# CAN1.net
KiCad netlist of a schematic drawn in Altium Designer
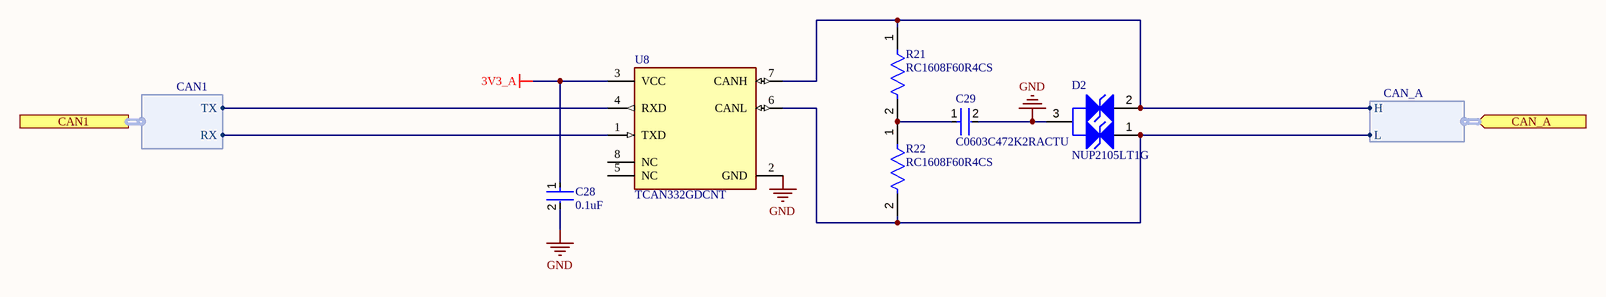
[diagram p0: CAN1.SchDoc]

(export (version "E")
  (design (tool "Eeschema 10.0.6"))
  (components
    (comp (ref "C28")
      (value "0.1uF")
      (footprint "FP-C0603C-CF-MFG")
      (description "CAP CER 0.1UF 50V X7R 0603")
      (fields (field (name "TOLERANCE") "0.1") (field (name "MANUFACTURER") "KEMET"))
      (libsource (lib "Altium Content Vault") (part "b4654b650e69147ec39a6b967a45e02"))
    )
    (comp (ref "C29")
      (value "C0603C472K2RACTU")
      (footprint "FP-C0603C-CF-MFG")
      (description "CAP CER 4700PF 200V 10% X7R 0603")
      (fields
        (field (name "OCTOPART") "https://octopart.com/c0603c472k2ractu-kemet-17058096")
        (field (name "MANUFACTURER") "KEMET")
      )
      (libsource (lib "Altium Content Vault") (part "b4654b650e69147ec39a6b967a45e02"))
    )
    (comp (ref "D2")
      (value "NUP2105LT1G")
      (footprint "ONSC-SOT-23-3-318-08_V")
      (description "Dual Line CAN Bus Protector, 3-Pin SOT-23, Pb-Free, Tape and Reel")
      (fields (field (name "MANUFACTURER") "On Semiconductor"))
      (libsource (lib "Altium Content Vault") (part "ONSC-NUP21X5X-SOT-23-3-318-08"))
    )
    (comp (ref "R21")
      (value "RC1608F60R4CS")
      (footprint "FP-RC1608-IPC_C")
      (description "Res Thick Film 0603 60.4Ω 1% 0.1W ±100ppm/°C Molded SMD T/R")
      (fields (field (name "TOLERANCE") "1%"))
      (libsource (lib "Altium Content Vault") (part "1029c3af85768c4190bb7ad29bc67b5"))
    )
    (comp (ref "R22")
      (value "RC1608F60R4CS")
      (footprint "FP-RC1608-IPC_C")
      (description "Res Thick Film 0603 60.4Ω 1% 0.1W ±100ppm/°C Molded SMD T/R")
      (fields (field (name "TOLERANCE") "1%"))
      (libsource (lib "Altium Content Vault") (part "1029c3af85768c4190bb7ad29bc67b5"))
    )
    (comp (ref "U8")
      (value "TCAN332GDCNT")
      (footprint "FP-DCN0008A-IPC_C")
      (description "IC TRANSCEIVER 1/1 SOT23-8")
      (libsource (lib "Altium Content Vault") (part "f57d81afad401941ce556981ca48666"))
    )
  )
  (nets
    (net (code "3") (name "/H") (class "Default")
      (node (ref "D2") (pin "2") (pinfunction "K_2") (pintype "passive"))
      (node (ref "R21") (pin "1") (pinfunction "1_1") (pintype "passive"))
      (node (ref "U8") (pin "7") (pinfunction "CANH_7") (pintype "bidirectional"))
    )
    (net (code "4") (name "/L") (class "Default")
      (node (ref "D2") (pin "1") (pinfunction "K_1") (pintype "passive"))
      (node (ref "R22") (pin "2") (pinfunction "2_2") (pintype "passive"))
      (node (ref "U8") (pin "6") (pinfunction "CANL_6") (pintype "bidirectional"))
    )
    (net (code "5") (name "/RX") (class "Default")
      (node (ref "U8") (pin "1") (pinfunction "TXD_1") (pintype "input"))
    )
    (net (code "6") (name "/TX") (class "Default")
      (node (ref "U8") (pin "4") (pinfunction "RXD_4") (pintype "output"))
    )
    (net (code "9") (name "3V3_A") (class "Default")
      (node (ref "C28") (pin "1") (pinfunction "1_1") (pintype "passive"))
      (node (ref "U8") (pin "3") (pinfunction "VCC_3") (pintype "power_in"))
    )
    (net (code "10") (name "GND") (class "Default")
      (node (ref "C28") (pin "2") (pinfunction "2_2") (pintype "passive"))
      (node (ref "C29") (pin "2") (pinfunction "2_2") (pintype "passive"))
      (node (ref "D2") (pin "3") (pinfunction "K_3") (pintype "passive"))
      (node (ref "U8") (pin "2") (pinfunction "GND_2") (pintype "power_in"))
    )
    (net (code "11") (name "Net-(C29-Pad1)") (class "Default")
      (node (ref "C29") (pin "1") (pinfunction "1_1") (pintype "passive"))
      (node (ref "R21") (pin "2") (pinfunction "2_2") (pintype "passive"))
      (node (ref "R22") (pin "1") (pinfunction "1_1") (pintype "passive"))
    )
    (net (code "12") (name "unconnected-(U8-NC-Pad5)") (class "Default")
      (node (ref "U8") (pin "5") (pinfunction "NC_5") (pintype "passive"))
    )
    (net (code "13") (name "unconnected-(U8-NC-Pad8)") (class "Default")
      (node (ref "U8") (pin "8") (pinfunction "NC_8") (pintype "passive"))
    )
  )
)
